# SpineAlignPCB_1.net
KiCad netlist of a schematic drawn in EAGLE
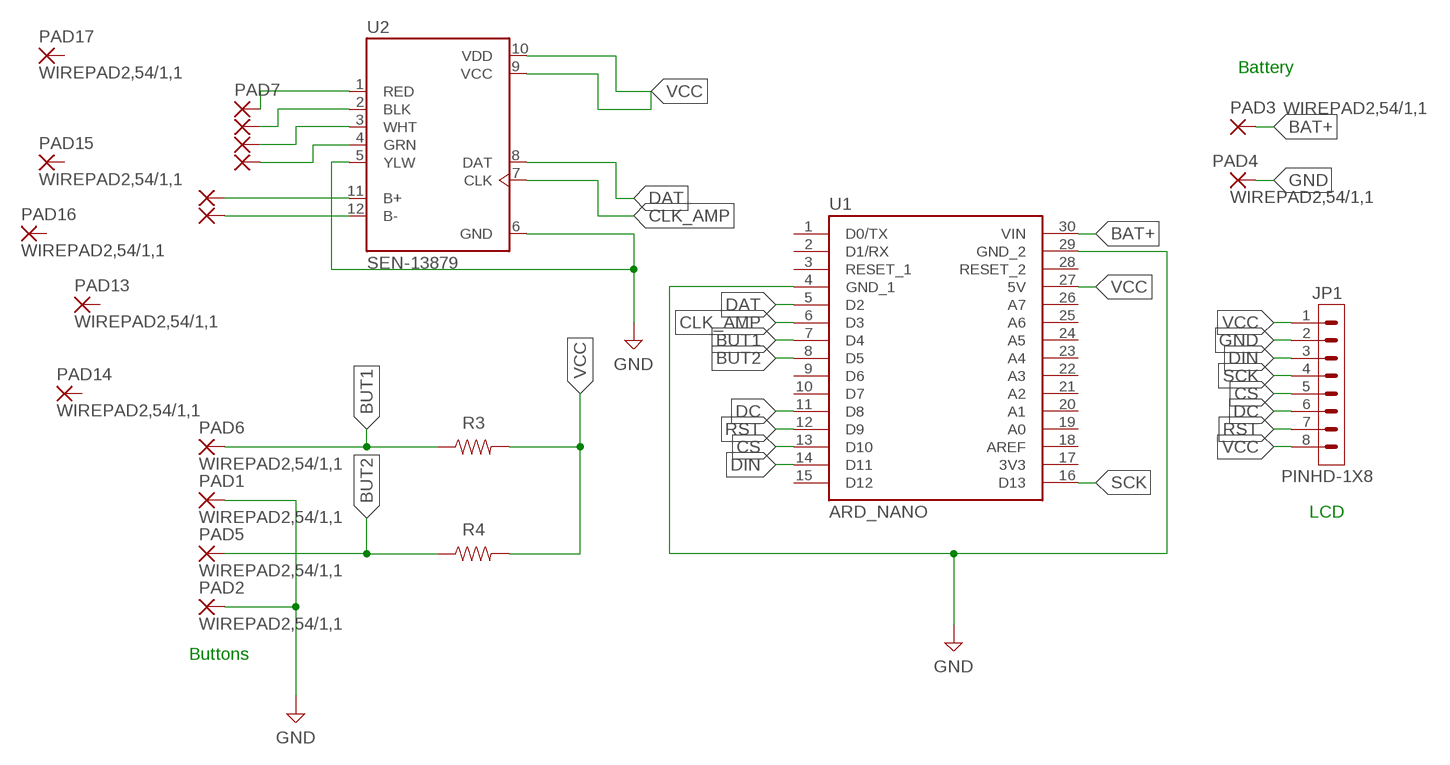
[diagram p0: schematic, sheet 1]

(export (version "E")
  (design (tool "Eeschema 10.0.6"))
  (components
    (comp (ref "JP1")
      (value "PINHD-1X8")
      (footprint "eagle-import:1X08")
      (libsource (lib "eagle-import") (part "PINHD-1X8"))
    )
    (comp (ref "PAD1")
      (value "WIREPAD2,54/1,1")
      (footprint "eagle-import:2,54_1,1")
      (libsource (lib "eagle-import") (part "WIREPAD2,54/1,1"))
    )
    (comp (ref "PAD2")
      (value "WIREPAD2,54/1,1")
      (footprint "eagle-import:2,54_1,1")
      (libsource (lib "eagle-import") (part "WIREPAD2,54/1,1"))
    )
    (comp (ref "PAD3")
      (value "WIREPAD2,54/1,1")
      (footprint "eagle-import:2,54_1,1")
      (libsource (lib "eagle-import") (part "WIREPAD2,54/1,1"))
    )
    (comp (ref "PAD4")
      (value "WIREPAD2,54/1,1")
      (footprint "eagle-import:2,54_1,1")
      (libsource (lib "eagle-import") (part "WIREPAD2,54/1,1"))
    )
    (comp (ref "PAD5")
      (value "WIREPAD2,54/1,1")
      (footprint "eagle-import:2,54_1,1")
      (libsource (lib "eagle-import") (part "WIREPAD2,54/1,1"))
    )
    (comp (ref "PAD6")
      (value "WIREPAD2,54/1,1")
      (footprint "eagle-import:2,54_1,1")
      (libsource (lib "eagle-import") (part "WIREPAD2,54/1,1"))
    )
    (comp (ref "PAD7")
      (value "WIREPAD2,54/1,1")
      (footprint "eagle-import:2,54_1,1")
      (libsource (lib "eagle-import") (part "WIREPAD2,54/1,1"))
    )
    (comp (ref "PAD8")
      (value "WIREPAD2,54/1,1")
      (footprint "eagle-import:2,54_1,1")
      (libsource (lib "eagle-import") (part "WIREPAD2,54/1,1"))
    )
    (comp (ref "PAD9")
      (value "WIREPAD2,54/1,1")
      (footprint "eagle-import:2,54_1,1")
      (libsource (lib "eagle-import") (part "WIREPAD2,54/1,1"))
    )
    (comp (ref "PAD10")
      (value "WIREPAD2,54/1,1")
      (footprint "eagle-import:2,54_1,1")
      (libsource (lib "eagle-import") (part "WIREPAD2,54/1,1"))
    )
    (comp (ref "PAD11")
      (value "WIREPAD2,54/1,1")
      (footprint "eagle-import:2,54_1,1")
      (libsource (lib "eagle-import") (part "WIREPAD2,54/1,1"))
    )
    (comp (ref "PAD12")
      (value "WIREPAD2,54/1,1")
      (footprint "eagle-import:2,54_1,1")
      (libsource (lib "eagle-import") (part "WIREPAD2,54/1,1"))
    )
    (comp (ref "PAD13")
      (value "WIREPAD2,54/1,1")
      (footprint "eagle-import:2,54_1,1")
      (libsource (lib "eagle-import") (part "WIREPAD2,54/1,1"))
    )
    (comp (ref "PAD14")
      (value "WIREPAD2,54/1,1")
      (footprint "eagle-import:2,54_1,1")
      (libsource (lib "eagle-import") (part "WIREPAD2,54/1,1"))
    )
    (comp (ref "PAD15")
      (value "WIREPAD2,54/1,1")
      (footprint "eagle-import:2,54_1,1")
      (libsource (lib "eagle-import") (part "WIREPAD2,54/1,1"))
    )
    (comp (ref "PAD16")
      (value "WIREPAD2,54/1,1")
      (footprint "eagle-import:2,54_1,1")
      (libsource (lib "eagle-import") (part "WIREPAD2,54/1,1"))
    )
    (comp (ref "PAD17")
      (value "WIREPAD2,54/1,1")
      (footprint "eagle-import:2,54_1,1")
      (libsource (lib "eagle-import") (part "WIREPAD2,54/1,1"))
    )
    (comp (ref "R3")
      (value "R-US_AXIAL-11.7MM-PITCH")
      (footprint "eagle-import:RESAD1176W63L850D250B")
      (libsource (lib "eagle-import") (part "R-USAXIAL-11.7MM-PITCH_"))
    )
    (comp (ref "R4")
      (value "R-US_AXIAL-11.7MM-PITCH")
      (footprint "eagle-import:RESAD1176W63L850D250B")
      (libsource (lib "eagle-import") (part "R-USAXIAL-11.7MM-PITCH_"))
    )
    (comp (ref "U1")
      (value "ARD_NANO")
      (footprint "eagle-import:MODULE_A000005")
      (fields (field (name "MANUFACTURER") "Arduino"))
      (libsource (lib "eagle-import") (part "ARD_NANO"))
    )
    (comp (ref "U2")
      (value "SEN-13879")
      (footprint "eagle-import:SPARKFUN_SEN-13879")
      (fields
        (field (name "DIGIKEY_PART_NUMBER") "1568-1436-ND")
        (field (name "MF") "Sparkfun Electronics")
        (field (name "MP") "SEN13879")
      )
      (libsource (lib "eagle-import") (part "SEN-13879"))
    )
  )
  (nets
    (net (code "1") (name "/3V3") (class "Default")
      (node (ref "U1") (pin "17") (pinfunction "3V3_17") (pintype "power_in"))
    )
    (net (code "2") (name "BAT+") (class "Default")
      (node (ref "PAD3") (pin "1") (pinfunction "P_1") (pintype "passive"))
      (node (ref "U1") (pin "30") (pinfunction "VIN_30") (pintype "power_in"))
    )
    (net (code "3") (name "BUT1") (class "Default")
      (node (ref "PAD6") (pin "1") (pinfunction "P_1") (pintype "passive"))
      (node (ref "R3") (pin "1") (pinfunction "1_1") (pintype "passive"))
      (node (ref "U1") (pin "7") (pinfunction "D4_7") (pintype "bidirectional"))
    )
    (net (code "4") (name "BUT2") (class "Default")
      (node (ref "PAD5") (pin "1") (pinfunction "P_1") (pintype "passive"))
      (node (ref "R4") (pin "1") (pinfunction "1_1") (pintype "passive"))
      (node (ref "U1") (pin "8") (pinfunction "D5_8") (pintype "bidirectional"))
    )
    (net (code "5") (name "CLK_AMP") (class "Default")
      (node (ref "U1") (pin "6") (pinfunction "D3_6") (pintype "bidirectional"))
      (node (ref "U2") (pin "7") (pinfunction "CLK_7") (pintype "input"))
    )
    (net (code "6") (name "CS") (class "Default")
      (node (ref "JP1") (pin "5") (pinfunction "5_5") (pintype "passive"))
      (node (ref "U1") (pin "13") (pinfunction "D10_13") (pintype "bidirectional"))
    )
    (net (code "7") (name "DAT") (class "Default")
      (node (ref "U1") (pin "5") (pinfunction "D2_5") (pintype "bidirectional"))
      (node (ref "U2") (pin "8") (pinfunction "DAT_8") (pintype "output"))
    )
    (net (code "8") (name "DC") (class "Default")
      (node (ref "JP1") (pin "6") (pinfunction "6_6") (pintype "passive"))
      (node (ref "U1") (pin "11") (pinfunction "D8_11") (pintype "bidirectional"))
    )
    (net (code "9") (name "DIN") (class "Default")
      (node (ref "JP1") (pin "3") (pinfunction "3_3") (pintype "passive"))
      (node (ref "U1") (pin "14") (pinfunction "D11_14") (pintype "bidirectional"))
    )
    (net (code "10") (name "GND") (class "Default")
      (node (ref "JP1") (pin "2") (pinfunction "2_2") (pintype "passive"))
      (node (ref "PAD1") (pin "1") (pinfunction "P_1") (pintype "passive"))
      (node (ref "PAD2") (pin "1") (pinfunction "P_1") (pintype "passive"))
      (node (ref "PAD4") (pin "1") (pinfunction "P_1") (pintype "passive"))
      (node (ref "U1") (pin "29") (pinfunction "GND_2_29") (pintype "power_in"))
      (node (ref "U1") (pin "4") (pinfunction "GND_1_4") (pintype "power_in"))
      (node (ref "U2") (pin "5") (pinfunction "YLW_5") (pintype "bidirectional"))
      (node (ref "U2") (pin "6") (pinfunction "GND_6") (pintype "power_in"))
    )
    (net (code "11") (name "Net-(PAD7-P)") (class "Default")
      (node (ref "PAD7") (pin "1") (pinfunction "P_1") (pintype "passive"))
      (node (ref "U2") (pin "1") (pinfunction "RED_1") (pintype "bidirectional"))
    )
    (net (code "12") (name "Net-(PAD8-P)") (class "Default")
      (node (ref "PAD8") (pin "1") (pinfunction "P_1") (pintype "passive"))
      (node (ref "U2") (pin "2") (pinfunction "BLK_2") (pintype "bidirectional"))
    )
    (net (code "13") (name "Net-(PAD9-P)") (class "Default")
      (node (ref "PAD9") (pin "1") (pinfunction "P_1") (pintype "passive"))
      (node (ref "U2") (pin "3") (pinfunction "WHT_3") (pintype "input"))
    )
    (net (code "14") (name "Net-(PAD10-P)") (class "Default")
      (node (ref "PAD10") (pin "1") (pinfunction "P_1") (pintype "passive"))
      (node (ref "U2") (pin "4") (pinfunction "GRN_4") (pintype "input"))
    )
    (net (code "15") (name "Net-(PAD11-P)") (class "Default")
      (node (ref "PAD11") (pin "1") (pinfunction "P_1") (pintype "passive"))
      (node (ref "U2") (pin "11") (pinfunction "B+_11") (pintype "input"))
    )
    (net (code "16") (name "Net-(PAD12-P)") (class "Default")
      (node (ref "PAD12") (pin "1") (pinfunction "P_1") (pintype "passive"))
      (node (ref "U2") (pin "12") (pinfunction "B-_12") (pintype "input"))
    )
    (net (code "17") (name "RST") (class "Default")
      (node (ref "JP1") (pin "7") (pinfunction "7_7") (pintype "passive"))
      (node (ref "U1") (pin "12") (pinfunction "D9_12") (pintype "bidirectional"))
    )
    (net (code "18") (name "SCK") (class "Default")
      (node (ref "JP1") (pin "4") (pinfunction "4_4") (pintype "passive"))
      (node (ref "U1") (pin "16") (pinfunction "D13_16") (pintype "bidirectional"))
    )
    (net (code "19") (name "VCC") (class "Default")
      (node (ref "JP1") (pin "1") (pinfunction "1_1") (pintype "passive"))
      (node (ref "JP1") (pin "8") (pinfunction "8_8") (pintype "passive"))
      (node (ref "R3") (pin "2") (pinfunction "2_2") (pintype "passive"))
      (node (ref "R4") (pin "2") (pinfunction "2_2") (pintype "passive"))
      (node (ref "U1") (pin "27") (pinfunction "5V_27") (pintype "power_in"))
      (node (ref "U2") (pin "10") (pinfunction "VDD_10") (pintype "power_in"))
      (node (ref "U2") (pin "9") (pinfunction "VCC_9") (pintype "power_in"))
    )
    (net (code "20") (name "unconnected-(PAD13-P-Pad1)") (class "Default")
      (node (ref "PAD13") (pin "1") (pinfunction "P_1") (pintype "passive"))
    )
    (net (code "21") (name "unconnected-(PAD14-P-Pad1)") (class "Default")
      (node (ref "PAD14") (pin "1") (pinfunction "P_1") (pintype "passive"))
    )
    (net (code "22") (name "unconnected-(PAD15-P-Pad1)") (class "Default")
      (node (ref "PAD15") (pin "1") (pinfunction "P_1") (pintype "passive"))
    )
    (net (code "23") (name "unconnected-(PAD16-P-Pad1)") (class "Default")
      (node (ref "PAD16") (pin "1") (pinfunction "P_1") (pintype "passive"))
    )
    (net (code "24") (name "unconnected-(PAD17-P-Pad1)") (class "Default")
      (node (ref "PAD17") (pin "1") (pinfunction "P_1") (pintype "passive"))
    )
    (net (code "25") (name "unconnected-(U1-A0-Pad19)") (class "Default")
      (node (ref "U1") (pin "19") (pinfunction "A0_19") (pintype "input"))
    )
    (net (code "26") (name "unconnected-(U1-A1-Pad20)") (class "Default")
      (node (ref "U1") (pin "20") (pinfunction "A1_20") (pintype "input"))
    )
    (net (code "27") (name "unconnected-(U1-A2-Pad21)") (class "Default")
      (node (ref "U1") (pin "21") (pinfunction "A2_21") (pintype "input"))
    )
    (net (code "28") (name "unconnected-(U1-A3-Pad22)") (class "Default")
      (node (ref "U1") (pin "22") (pinfunction "A3_22") (pintype "input"))
    )
    (net (code "29") (name "unconnected-(U1-A4-Pad23)") (class "Default")
      (node (ref "U1") (pin "23") (pinfunction "A4_23") (pintype "input"))
    )
    (net (code "30") (name "unconnected-(U1-A5-Pad24)") (class "Default")
      (node (ref "U1") (pin "24") (pinfunction "A5_24") (pintype "input"))
    )
    (net (code "31") (name "unconnected-(U1-A6-Pad25)") (class "Default")
      (node (ref "U1") (pin "25") (pinfunction "A6_25") (pintype "input"))
    )
    (net (code "32") (name "unconnected-(U1-A7-Pad26)") (class "Default")
      (node (ref "U1") (pin "26") (pinfunction "A7_26") (pintype "input"))
    )
    (net (code "33") (name "unconnected-(U1-AREF-Pad18)") (class "Default")
      (node (ref "U1") (pin "18") (pinfunction "AREF_18") (pintype "input"))
    )
    (net (code "34") (name "unconnected-(U1-D0{slash}TX-Pad1)") (class "Default")
      (node (ref "U1") (pin "1") (pinfunction "D0/TX_1") (pintype "bidirectional"))
    )
    (net (code "35") (name "unconnected-(U1-D1{slash}RX-Pad2)") (class "Default")
      (node (ref "U1") (pin "2") (pinfunction "D1/RX_2") (pintype "bidirectional"))
    )
    (net (code "36") (name "unconnected-(U1-D6-Pad9)") (class "Default")
      (node (ref "U1") (pin "9") (pinfunction "D6_9") (pintype "bidirectional"))
    )
    (net (code "37") (name "unconnected-(U1-D7-Pad10)") (class "Default")
      (node (ref "U1") (pin "10") (pinfunction "D7_10") (pintype "bidirectional"))
    )
    (net (code "38") (name "unconnected-(U1-D12-Pad15)") (class "Default")
      (node (ref "U1") (pin "15") (pinfunction "D12_15") (pintype "bidirectional"))
    )
    (net (code "39") (name "unconnected-(U1-RESET_1-Pad3)") (class "Default")
      (node (ref "U1") (pin "3") (pinfunction "RESET_1_3") (pintype "input"))
    )
    (net (code "40") (name "unconnected-(U1-RESET_2-Pad28)") (class "Default")
      (node (ref "U1") (pin "28") (pinfunction "RESET_2_28") (pintype "input"))
    )
  )
)
